# HighVBoard_02.net
KiCad netlist of a schematic drawn in EAGLE
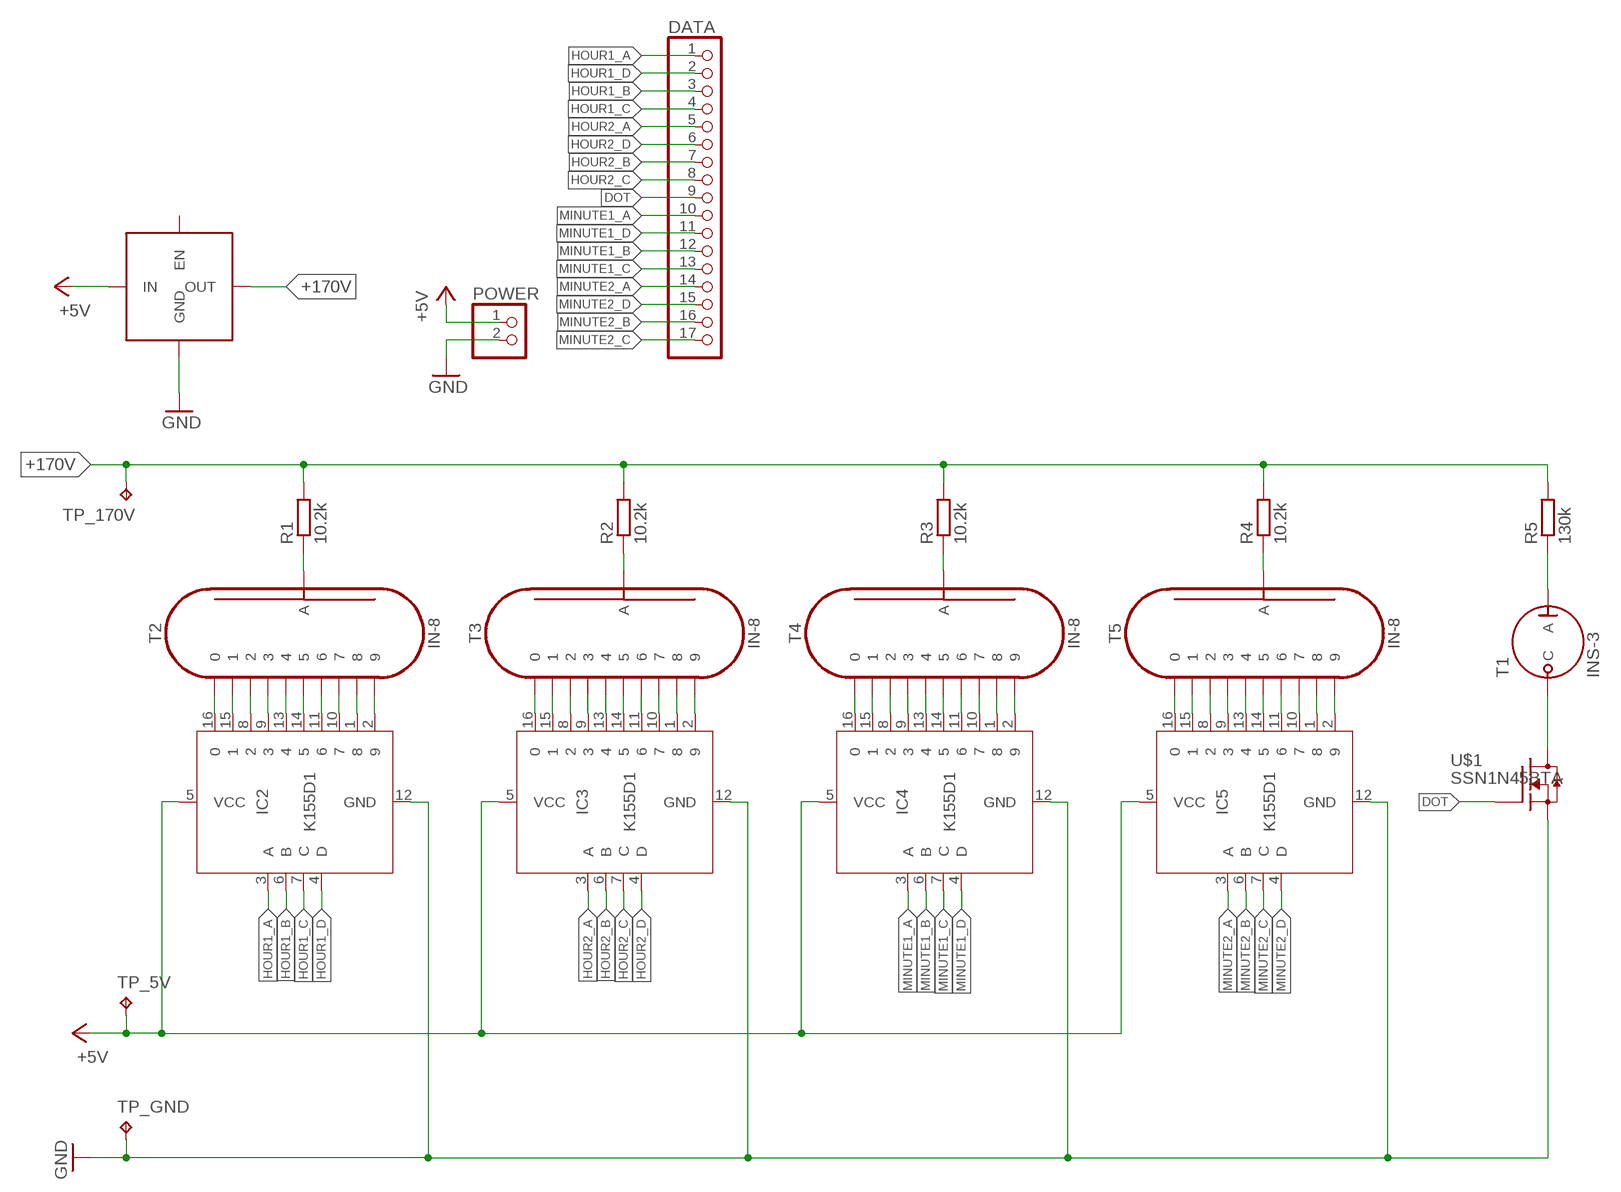
[diagram p0: schematic, sheet 1]

(export (version "E")
  (design (tool "Eeschema 10.0.6"))
  (components
    (comp (ref "DATA")
      (value "PINHD-1X17")
      (footprint "eagle-import:1X17")
      (libsource (lib "eagle-import") (part "PINHD-1X17"))
    )
    (comp (ref "IC2")
      (value "K155D1")
      (footprint "eagle-import:DIL16")
      (libsource (lib "eagle-import") (part "K155D1"))
    )
    (comp (ref "IC3")
      (value "K155D1")
      (footprint "eagle-import:DIL16")
      (libsource (lib "eagle-import") (part "K155D1"))
    )
    (comp (ref "IC4")
      (value "K155D1")
      (footprint "eagle-import:DIL16")
      (libsource (lib "eagle-import") (part "K155D1"))
    )
    (comp (ref "IC5")
      (value "K155D1")
      (footprint "eagle-import:DIL16")
      (libsource (lib "eagle-import") (part "K155D1"))
    )
    (comp (ref "POWER")
      (value "PINHD-1X2")
      (footprint "eagle-import:1X02")
      (libsource (lib "eagle-import") (part "PINHD-1X2"))
    )
    (comp (ref "R1")
      (value "10.2k")
      (footprint "eagle-import:0207_10")
      (libsource (lib "eagle-import") (part "R-EU_0207/10"))
    )
    (comp (ref "R2")
      (value "10.2k")
      (footprint "eagle-import:0207_10")
      (libsource (lib "eagle-import") (part "R-EU_0207/10"))
    )
    (comp (ref "R3")
      (value "10.2k")
      (footprint "eagle-import:0207_10")
      (libsource (lib "eagle-import") (part "R-EU_0207/10"))
    )
    (comp (ref "R4")
      (value "10.2k")
      (footprint "eagle-import:0207_10")
      (libsource (lib "eagle-import") (part "R-EU_0207/10"))
    )
    (comp (ref "R5")
      (value "130k")
      (footprint "eagle-import:0207_10")
      (libsource (lib "eagle-import") (part "R-EU_0207/10"))
    )
    (comp (ref "T1")
      (value "INS-3")
      (footprint "eagle-import:INS-3")
      (libsource (lib "eagle-import") (part "INS-3"))
    )
    (comp (ref "T2")
      (value "IN-8")
      (footprint "eagle-import:IN-8")
      (libsource (lib "eagle-import") (part "IN-8"))
    )
    (comp (ref "T3")
      (value "IN-8")
      (footprint "eagle-import:IN-8")
      (libsource (lib "eagle-import") (part "IN-8"))
    )
    (comp (ref "T4")
      (value "IN-8")
      (footprint "eagle-import:IN-8")
      (libsource (lib "eagle-import") (part "IN-8"))
    )
    (comp (ref "T5")
      (value "IN-8")
      (footprint "eagle-import:IN-8")
      (libsource (lib "eagle-import") (part "IN-8"))
    )
    (comp (ref "TP_5V")
      (value "TPPAD1-13")
      (footprint "eagle-import:P1-13")
      (libsource (lib "eagle-import") (part "TPPAD1-13"))
    )
    (comp (ref "TP_170V")
      (value "TPPAD1-13")
      (footprint "eagle-import:P1-13")
      (libsource (lib "eagle-import") (part "TPPAD1-13"))
    )
    (comp (ref "TP_GND")
      (value "TPPAD1-13")
      (footprint "eagle-import:P1-13")
      (libsource (lib "eagle-import") (part "TPPAD1-13"))
    )
    (comp (ref "U$1")
      (value "SSN1N45BTA")
      (footprint "eagle-import:TO92")
      (libsource (lib "eagle-import") (part "SSN1N45BTA"))
    )
    (comp (ref "U$2")
      (value "NIXIE-PSU")
      (footprint "eagle-import:NIXIE-PSU")
      (libsource (lib "eagle-import") (part "NIXIE-PSU"))
    )
  )
  (nets
    (net (code "1") (name "+5V") (class "Default")
      (node (ref "IC2") (pin "5") (pinfunction "VCC_5") (pintype "bidirectional"))
      (node (ref "IC3") (pin "5") (pinfunction "VCC_5") (pintype "bidirectional"))
      (node (ref "IC4") (pin "5") (pinfunction "VCC_5") (pintype "bidirectional"))
      (node (ref "IC5") (pin "5") (pinfunction "VCC_5") (pintype "bidirectional"))
      (node (ref "POWER") (pin "1") (pinfunction "1_1") (pintype "passive"))
      (node (ref "TP_5V") (pin "TP") (pinfunction "TP_TP") (pintype "input"))
      (node (ref "U$2") (pin "1") (pinfunction "IN_1") (pintype "bidirectional"))
    )
    (net (code "2") (name "+170V") (class "Default")
      (node (ref "R1") (pin "2") (pinfunction "2_2") (pintype "passive"))
      (node (ref "R2") (pin "2") (pinfunction "2_2") (pintype "passive"))
      (node (ref "R3") (pin "2") (pinfunction "2_2") (pintype "passive"))
      (node (ref "R4") (pin "2") (pinfunction "2_2") (pintype "passive"))
      (node (ref "R5") (pin "2") (pinfunction "2_2") (pintype "passive"))
      (node (ref "TP_170V") (pin "TP") (pinfunction "TP_TP") (pintype "input"))
      (node (ref "U$2") (pin "5") (pinfunction "OUT_5") (pintype "bidirectional"))
    )
    (net (code "3") (name "DOT") (class "Default")
      (node (ref "DATA") (pin "9") (pinfunction "9_9") (pintype "passive"))
      (node (ref "U$1") (pin "1") (pinfunction "G_1") (pintype "passive"))
    )
    (net (code "4") (name "GND") (class "Default")
      (node (ref "IC2") (pin "12") (pinfunction "GND_12") (pintype "bidirectional"))
      (node (ref "IC3") (pin "12") (pinfunction "GND_12") (pintype "bidirectional"))
      (node (ref "IC4") (pin "12") (pinfunction "GND_12") (pintype "bidirectional"))
      (node (ref "IC5") (pin "12") (pinfunction "GND_12") (pintype "bidirectional"))
      (node (ref "POWER") (pin "2") (pinfunction "2_2") (pintype "passive"))
      (node (ref "TP_GND") (pin "TP") (pinfunction "TP_TP") (pintype "input"))
      (node (ref "U$1") (pin "3") (pinfunction "S_3") (pintype "passive"))
      (node (ref "U$2") (pin "2") (pinfunction "GND_2") (pintype "bidirectional"))
      (node (ref "U$2") (pin "4") (pinfunction "GND_4") (pintype "bidirectional"))
    )
    (net (code "5") (name "HOUR1_A") (class "Default")
      (node (ref "DATA") (pin "1") (pinfunction "1_1") (pintype "passive"))
      (node (ref "IC2") (pin "3") (pinfunction "A_3") (pintype "bidirectional"))
    )
    (net (code "6") (name "HOUR1_B") (class "Default")
      (node (ref "DATA") (pin "3") (pinfunction "3_3") (pintype "passive"))
      (node (ref "IC2") (pin "6") (pinfunction "B_6") (pintype "bidirectional"))
    )
    (net (code "7") (name "HOUR1_C") (class "Default")
      (node (ref "DATA") (pin "4") (pinfunction "4_4") (pintype "passive"))
      (node (ref "IC2") (pin "7") (pinfunction "C_7") (pintype "bidirectional"))
    )
    (net (code "8") (name "HOUR1_D") (class "Default")
      (node (ref "DATA") (pin "2") (pinfunction "2_2") (pintype "passive"))
      (node (ref "IC2") (pin "4") (pinfunction "D_4") (pintype "bidirectional"))
    )
    (net (code "9") (name "HOUR2_A") (class "Default")
      (node (ref "DATA") (pin "5") (pinfunction "5_5") (pintype "passive"))
      (node (ref "IC3") (pin "3") (pinfunction "A_3") (pintype "bidirectional"))
    )
    (net (code "10") (name "HOUR2_B") (class "Default")
      (node (ref "DATA") (pin "7") (pinfunction "7_7") (pintype "passive"))
      (node (ref "IC3") (pin "6") (pinfunction "B_6") (pintype "bidirectional"))
    )
    (net (code "11") (name "HOUR2_C") (class "Default")
      (node (ref "DATA") (pin "8") (pinfunction "8_8") (pintype "passive"))
      (node (ref "IC3") (pin "7") (pinfunction "C_7") (pintype "bidirectional"))
    )
    (net (code "12") (name "HOUR2_D") (class "Default")
      (node (ref "DATA") (pin "6") (pinfunction "6_6") (pintype "passive"))
      (node (ref "IC3") (pin "4") (pinfunction "D_4") (pintype "bidirectional"))
    )
    (net (code "13") (name "MINUTE1_A") (class "Default")
      (node (ref "DATA") (pin "10") (pinfunction "10_10") (pintype "passive"))
      (node (ref "IC4") (pin "3") (pinfunction "A_3") (pintype "bidirectional"))
    )
    (net (code "14") (name "MINUTE1_B") (class "Default")
      (node (ref "DATA") (pin "12") (pinfunction "12_12") (pintype "passive"))
      (node (ref "IC4") (pin "6") (pinfunction "B_6") (pintype "bidirectional"))
    )
    (net (code "15") (name "MINUTE1_C") (class "Default")
      (node (ref "DATA") (pin "13") (pinfunction "13_13") (pintype "passive"))
      (node (ref "IC4") (pin "7") (pinfunction "C_7") (pintype "bidirectional"))
    )
    (net (code "16") (name "MINUTE1_D") (class "Default")
      (node (ref "DATA") (pin "11") (pinfunction "11_11") (pintype "passive"))
      (node (ref "IC4") (pin "4") (pinfunction "D_4") (pintype "bidirectional"))
    )
    (net (code "17") (name "MINUTE2_A") (class "Default")
      (node (ref "DATA") (pin "14") (pinfunction "14_14") (pintype "passive"))
      (node (ref "IC5") (pin "3") (pinfunction "A_3") (pintype "bidirectional"))
    )
    (net (code "18") (name "MINUTE2_B") (class "Default")
      (node (ref "DATA") (pin "16") (pinfunction "16_16") (pintype "passive"))
      (node (ref "IC5") (pin "6") (pinfunction "B_6") (pintype "bidirectional"))
    )
    (net (code "19") (name "MINUTE2_C") (class "Default")
      (node (ref "DATA") (pin "17") (pinfunction "17_17") (pintype "passive"))
      (node (ref "IC5") (pin "7") (pinfunction "C_7") (pintype "bidirectional"))
    )
    (net (code "20") (name "MINUTE2_D") (class "Default")
      (node (ref "DATA") (pin "15") (pinfunction "15_15") (pintype "passive"))
      (node (ref "IC5") (pin "4") (pinfunction "D_4") (pintype "bidirectional"))
    )
    (net (code "21") (name "Net-(IC2-0)") (class "Default")
      (node (ref "IC2") (pin "16") (pinfunction "0_16") (pintype "bidirectional"))
      (node (ref "T2") (pin "10") (pinfunction "0_10") (pintype "bidirectional"))
    )
    (net (code "22") (name "Net-(IC2-1)") (class "Default")
      (node (ref "IC2") (pin "15") (pinfunction "1_15") (pintype "bidirectional"))
      (node (ref "T2") (pin "1") (pinfunction "1_1") (pintype "bidirectional"))
    )
    (net (code "23") (name "Net-(IC2-2)") (class "Default")
      (node (ref "IC2") (pin "8") (pinfunction "2_8") (pintype "bidirectional"))
      (node (ref "T2") (pin "2") (pinfunction "2_2") (pintype "bidirectional"))
    )
    (net (code "24") (name "Net-(IC2-3)") (class "Default")
      (node (ref "IC2") (pin "9") (pinfunction "3_9") (pintype "bidirectional"))
      (node (ref "T2") (pin "3") (pinfunction "3_3") (pintype "bidirectional"))
    )
    (net (code "25") (name "Net-(IC2-4)") (class "Default")
      (node (ref "IC2") (pin "13") (pinfunction "4_13") (pintype "bidirectional"))
      (node (ref "T2") (pin "4") (pinfunction "4_4") (pintype "bidirectional"))
    )
    (net (code "26") (name "Net-(IC2-5)") (class "Default")
      (node (ref "IC2") (pin "14") (pinfunction "5_14") (pintype "bidirectional"))
      (node (ref "T2") (pin "5") (pinfunction "5_5") (pintype "bidirectional"))
    )
    (net (code "27") (name "Net-(IC2-6)") (class "Default")
      (node (ref "IC2") (pin "11") (pinfunction "6_11") (pintype "bidirectional"))
      (node (ref "T2") (pin "6") (pinfunction "6_6") (pintype "bidirectional"))
    )
    (net (code "28") (name "Net-(IC2-7)") (class "Default")
      (node (ref "IC2") (pin "10") (pinfunction "7_10") (pintype "bidirectional"))
      (node (ref "T2") (pin "7") (pinfunction "7_7") (pintype "bidirectional"))
    )
    (net (code "29") (name "Net-(IC2-8)") (class "Default")
      (node (ref "IC2") (pin "1") (pinfunction "8_1") (pintype "bidirectional"))
      (node (ref "T2") (pin "8") (pinfunction "8_8") (pintype "bidirectional"))
    )
    (net (code "30") (name "Net-(IC2-9)") (class "Default")
      (node (ref "IC2") (pin "2") (pinfunction "9_2") (pintype "bidirectional"))
      (node (ref "T2") (pin "9") (pinfunction "9_9") (pintype "bidirectional"))
    )
    (net (code "31") (name "Net-(IC3-0)") (class "Default")
      (node (ref "IC3") (pin "16") (pinfunction "0_16") (pintype "bidirectional"))
      (node (ref "T3") (pin "10") (pinfunction "0_10") (pintype "bidirectional"))
    )
    (net (code "32") (name "Net-(IC3-1)") (class "Default")
      (node (ref "IC3") (pin "15") (pinfunction "1_15") (pintype "bidirectional"))
      (node (ref "T3") (pin "1") (pinfunction "1_1") (pintype "bidirectional"))
    )
    (net (code "33") (name "Net-(IC3-2)") (class "Default")
      (node (ref "IC3") (pin "8") (pinfunction "2_8") (pintype "bidirectional"))
      (node (ref "T3") (pin "2") (pinfunction "2_2") (pintype "bidirectional"))
    )
    (net (code "34") (name "Net-(IC3-3)") (class "Default")
      (node (ref "IC3") (pin "9") (pinfunction "3_9") (pintype "bidirectional"))
      (node (ref "T3") (pin "3") (pinfunction "3_3") (pintype "bidirectional"))
    )
    (net (code "35") (name "Net-(IC3-4)") (class "Default")
      (node (ref "IC3") (pin "13") (pinfunction "4_13") (pintype "bidirectional"))
      (node (ref "T3") (pin "4") (pinfunction "4_4") (pintype "bidirectional"))
    )
    (net (code "36") (name "Net-(IC3-5)") (class "Default")
      (node (ref "IC3") (pin "14") (pinfunction "5_14") (pintype "bidirectional"))
      (node (ref "T3") (pin "5") (pinfunction "5_5") (pintype "bidirectional"))
    )
    (net (code "37") (name "Net-(IC3-6)") (class "Default")
      (node (ref "IC3") (pin "11") (pinfunction "6_11") (pintype "bidirectional"))
      (node (ref "T3") (pin "6") (pinfunction "6_6") (pintype "bidirectional"))
    )
    (net (code "38") (name "Net-(IC3-7)") (class "Default")
      (node (ref "IC3") (pin "10") (pinfunction "7_10") (pintype "bidirectional"))
      (node (ref "T3") (pin "7") (pinfunction "7_7") (pintype "bidirectional"))
    )
    (net (code "39") (name "Net-(IC3-8)") (class "Default")
      (node (ref "IC3") (pin "1") (pinfunction "8_1") (pintype "bidirectional"))
      (node (ref "T3") (pin "8") (pinfunction "8_8") (pintype "bidirectional"))
    )
    (net (code "40") (name "Net-(IC3-9)") (class "Default")
      (node (ref "IC3") (pin "2") (pinfunction "9_2") (pintype "bidirectional"))
      (node (ref "T3") (pin "9") (pinfunction "9_9") (pintype "bidirectional"))
    )
    (net (code "41") (name "Net-(IC4-0)") (class "Default")
      (node (ref "IC4") (pin "16") (pinfunction "0_16") (pintype "bidirectional"))
      (node (ref "T4") (pin "10") (pinfunction "0_10") (pintype "bidirectional"))
    )
    (net (code "42") (name "Net-(IC4-1)") (class "Default")
      (node (ref "IC4") (pin "15") (pinfunction "1_15") (pintype "bidirectional"))
      (node (ref "T4") (pin "1") (pinfunction "1_1") (pintype "bidirectional"))
    )
    (net (code "43") (name "Net-(IC4-2)") (class "Default")
      (node (ref "IC4") (pin "8") (pinfunction "2_8") (pintype "bidirectional"))
      (node (ref "T4") (pin "2") (pinfunction "2_2") (pintype "bidirectional"))
    )
    (net (code "44") (name "Net-(IC4-3)") (class "Default")
      (node (ref "IC4") (pin "9") (pinfunction "3_9") (pintype "bidirectional"))
      (node (ref "T4") (pin "3") (pinfunction "3_3") (pintype "bidirectional"))
    )
    (net (code "45") (name "Net-(IC4-4)") (class "Default")
      (node (ref "IC4") (pin "13") (pinfunction "4_13") (pintype "bidirectional"))
      (node (ref "T4") (pin "4") (pinfunction "4_4") (pintype "bidirectional"))
    )
    (net (code "46") (name "Net-(IC4-5)") (class "Default")
      (node (ref "IC4") (pin "14") (pinfunction "5_14") (pintype "bidirectional"))
      (node (ref "T4") (pin "5") (pinfunction "5_5") (pintype "bidirectional"))
    )
    (net (code "47") (name "Net-(IC4-6)") (class "Default")
      (node (ref "IC4") (pin "11") (pinfunction "6_11") (pintype "bidirectional"))
      (node (ref "T4") (pin "6") (pinfunction "6_6") (pintype "bidirectional"))
    )
    (net (code "48") (name "Net-(IC4-7)") (class "Default")
      (node (ref "IC4") (pin "10") (pinfunction "7_10") (pintype "bidirectional"))
      (node (ref "T4") (pin "7") (pinfunction "7_7") (pintype "bidirectional"))
    )
    (net (code "49") (name "Net-(IC4-8)") (class "Default")
      (node (ref "IC4") (pin "1") (pinfunction "8_1") (pintype "bidirectional"))
      (node (ref "T4") (pin "8") (pinfunction "8_8") (pintype "bidirectional"))
    )
    (net (code "50") (name "Net-(IC4-9)") (class "Default")
      (node (ref "IC4") (pin "2") (pinfunction "9_2") (pintype "bidirectional"))
      (node (ref "T4") (pin "9") (pinfunction "9_9") (pintype "bidirectional"))
    )
    (net (code "51") (name "Net-(IC5-0)") (class "Default")
      (node (ref "IC5") (pin "16") (pinfunction "0_16") (pintype "bidirectional"))
      (node (ref "T5") (pin "10") (pinfunction "0_10") (pintype "bidirectional"))
    )
    (net (code "52") (name "Net-(IC5-1)") (class "Default")
      (node (ref "IC5") (pin "15") (pinfunction "1_15") (pintype "bidirectional"))
      (node (ref "T5") (pin "1") (pinfunction "1_1") (pintype "bidirectional"))
    )
    (net (code "53") (name "Net-(IC5-2)") (class "Default")
      (node (ref "IC5") (pin "8") (pinfunction "2_8") (pintype "bidirectional"))
      (node (ref "T5") (pin "2") (pinfunction "2_2") (pintype "bidirectional"))
    )
    (net (code "54") (name "Net-(IC5-3)") (class "Default")
      (node (ref "IC5") (pin "9") (pinfunction "3_9") (pintype "bidirectional"))
      (node (ref "T5") (pin "3") (pinfunction "3_3") (pintype "bidirectional"))
    )
    (net (code "55") (name "Net-(IC5-4)") (class "Default")
      (node (ref "IC5") (pin "13") (pinfunction "4_13") (pintype "bidirectional"))
      (node (ref "T5") (pin "4") (pinfunction "4_4") (pintype "bidirectional"))
    )
    (net (code "56") (name "Net-(IC5-5)") (class "Default")
      (node (ref "IC5") (pin "14") (pinfunction "5_14") (pintype "bidirectional"))
      (node (ref "T5") (pin "5") (pinfunction "5_5") (pintype "bidirectional"))
    )
    (net (code "57") (name "Net-(IC5-6)") (class "Default")
      (node (ref "IC5") (pin "11") (pinfunction "6_11") (pintype "bidirectional"))
      (node (ref "T5") (pin "6") (pinfunction "6_6") (pintype "bidirectional"))
    )
    (net (code "58") (name "Net-(IC5-7)") (class "Default")
      (node (ref "IC5") (pin "10") (pinfunction "7_10") (pintype "bidirectional"))
      (node (ref "T5") (pin "7") (pinfunction "7_7") (pintype "bidirectional"))
    )
    (net (code "59") (name "Net-(IC5-8)") (class "Default")
      (node (ref "IC5") (pin "1") (pinfunction "8_1") (pintype "bidirectional"))
      (node (ref "T5") (pin "8") (pinfunction "8_8") (pintype "bidirectional"))
    )
    (net (code "60") (name "Net-(IC5-9)") (class "Default")
      (node (ref "IC5") (pin "2") (pinfunction "9_2") (pintype "bidirectional"))
      (node (ref "T5") (pin "9") (pinfunction "9_9") (pintype "bidirectional"))
    )
    (net (code "61") (name "Net-(R1-Pad1)") (class "Default")
      (node (ref "R1") (pin "1") (pinfunction "1_1") (pintype "passive"))
      (node (ref "T2") (pin "A") (pinfunction "A_A") (pintype "bidirectional"))
    )
    (net (code "62") (name "Net-(R2-Pad1)") (class "Default")
      (node (ref "R2") (pin "1") (pinfunction "1_1") (pintype "passive"))
      (node (ref "T3") (pin "A") (pinfunction "A_A") (pintype "bidirectional"))
    )
    (net (code "63") (name "Net-(R3-Pad1)") (class "Default")
      (node (ref "R3") (pin "1") (pinfunction "1_1") (pintype "passive"))
      (node (ref "T4") (pin "A") (pinfunction "A_A") (pintype "bidirectional"))
    )
    (net (code "64") (name "Net-(R4-Pad1)") (class "Default")
      (node (ref "R4") (pin "1") (pinfunction "1_1") (pintype "passive"))
      (node (ref "T5") (pin "A") (pinfunction "A_A") (pintype "bidirectional"))
    )
    (net (code "65") (name "Net-(R5-Pad1)") (class "Default")
      (node (ref "R5") (pin "1") (pinfunction "1_1") (pintype "passive"))
      (node (ref "T1") (pin "A") (pinfunction "A_A") (pintype "bidirectional"))
    )
    (net (code "66") (name "Net-(U$1-D)") (class "Default")
      (node (ref "T1") (pin "C") (pinfunction "C_C") (pintype "bidirectional"))
      (node (ref "U$1") (pin "2") (pinfunction "D_2") (pintype "passive"))
    )
    (net (code "67") (name "unconnected-(U$2-EN-Pad3)") (class "Default")
      (node (ref "U$2") (pin "3") (pinfunction "EN_3") (pintype "bidirectional"))
    )
  )
)
